# UART_BUS.net
KiCad netlist of a schematic drawn in Altium Designer
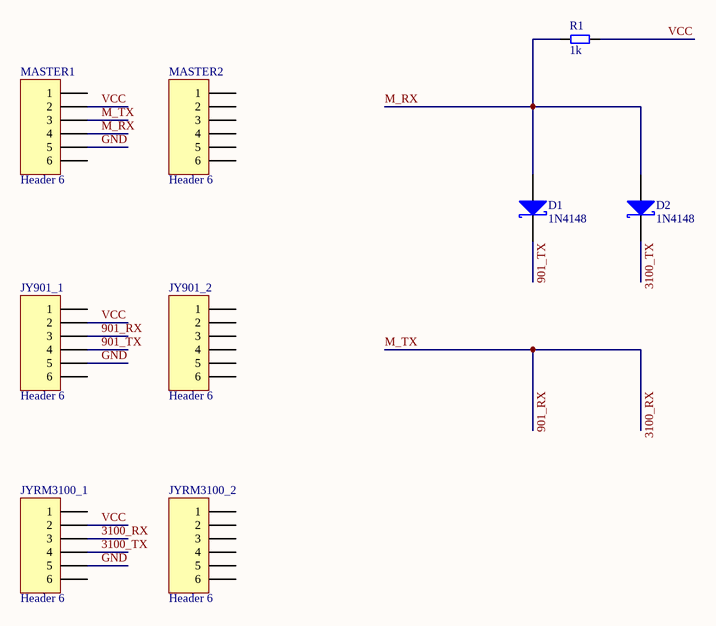
[diagram p0: UART_BUS.SchDoc]

(export (version "E")
  (design (tool "Eeschema 10.0.6"))
  (components
    (comp (ref "D1")
      (value "1N4148")
      (footprint "1N4148_S")
      (description "Schottky Diode")
      (fields (field (name "PUBLISHER") "Altium Limited"))
      (libsource (lib "mosdirver") (part "D Schottky"))
    )
    (comp (ref "D2")
      (value "1N4148")
      (footprint "1N4148_S")
      (description "Schottky Diode")
      (fields (field (name "PUBLISHER") "Altium Limited"))
      (libsource (lib "mosdirver") (part "D Schottky"))
    )
    (comp (ref "JY901_1")
      (value "Device Name")
      (footprint "HDR1X6")
      (description "Header, 6-Pin")
      (fields (field (name "SCH NAME") "Header 6"))
      (libsource (lib "Connector") (part "Header 6"))
    )
    (comp (ref "JY901_2")
      (value "Device Name")
      (footprint "HDR1X6")
      (description "Header, 6-Pin")
      (fields (field (name "SCH NAME") "Header 6"))
      (libsource (lib "Connector") (part "Header 6"))
    )
    (comp (ref "JYRM3100_1")
      (value "Device Name")
      (footprint "HDR1X6")
      (description "Header, 6-Pin")
      (fields (field (name "SCH NAME") "Header 6"))
      (libsource (lib "Connector") (part "Header 6"))
    )
    (comp (ref "JYRM3100_2")
      (value "Device Name")
      (footprint "HDR1X6")
      (description "Header, 6-Pin")
      (fields (field (name "SCH NAME") "Header 6"))
      (libsource (lib "Connector") (part "Header 6"))
    )
    (comp (ref "MASTER1")
      (value "Device Name")
      (footprint "HDR1X6")
      (description "Header, 6-Pin")
      (fields (field (name "SCH NAME") "Header 6"))
      (libsource (lib "Connector") (part "Header 6"))
    )
    (comp (ref "MASTER2")
      (value "Device Name")
      (footprint "HDR1X6")
      (description "Header, 6-Pin")
      (fields (field (name "SCH NAME") "Header 6"))
      (libsource (lib "Connector") (part "Header 6"))
    )
    (comp (ref "R1")
      (value "xxR/Precision/Footprint")
      (footprint "RES 0603")
      (description "Resistor Chip")
      (fields (field (name "SCH NAME") "1k"))
      (libsource (lib "Basal") (part "Resistor Chip"))
    )
  )
  (nets
    (net (code "1") (name "/901_TX") (class "Default")
      (node (ref "D1") (pin "2") (pinfunction "K_2") (pintype "passive"))
      (node (ref "JY901_1") (pin "4") (pinfunction "4_4") (pintype "passive"))
    )
    (net (code "2") (name "/3100_RX") (class "Default")
      (node (ref "JY901_1") (pin "3") (pinfunction "3_3") (pintype "passive"))
      (node (ref "JYRM3100_1") (pin "3") (pinfunction "3_3") (pintype "passive"))
      (node (ref "MASTER1") (pin "3") (pinfunction "3_3") (pintype "passive"))
    )
    (net (code "3") (name "/3100_TX") (class "Default")
      (node (ref "D2") (pin "2") (pinfunction "K_2") (pintype "passive"))
      (node (ref "JYRM3100_1") (pin "4") (pinfunction "4_4") (pintype "passive"))
    )
    (net (code "4") (name "/GND") (class "Default")
      (node (ref "JY901_1") (pin "5") (pinfunction "5_5") (pintype "passive"))
      (node (ref "JYRM3100_1") (pin "5") (pinfunction "5_5") (pintype "passive"))
      (node (ref "MASTER1") (pin "5") (pinfunction "5_5") (pintype "passive"))
    )
    (net (code "5") (name "/M_RX") (class "Default")
      (node (ref "D1") (pin "1") (pinfunction "A_1") (pintype "passive"))
      (node (ref "D2") (pin "1") (pinfunction "A_1") (pintype "passive"))
      (node (ref "MASTER1") (pin "4") (pinfunction "4_4") (pintype "passive"))
      (node (ref "R1") (pin "1") (pintype "passive"))
    )
    (net (code "6") (name "/VCC") (class "Default")
      (node (ref "JY901_1") (pin "2") (pinfunction "2_2") (pintype "passive"))
      (node (ref "JYRM3100_1") (pin "2") (pinfunction "2_2") (pintype "passive"))
      (node (ref "MASTER1") (pin "2") (pinfunction "2_2") (pintype "passive"))
      (node (ref "R1") (pin "2") (pintype "passive"))
    )
    (net (code "7") (name "unconnected-(JY901_1-Pad1)") (class "Default")
      (node (ref "JY901_1") (pin "1") (pinfunction "1_1") (pintype "passive"))
    )
    (net (code "8") (name "unconnected-(JY901_1-Pad6)") (class "Default")
      (node (ref "JY901_1") (pin "6") (pinfunction "6_6") (pintype "passive"))
    )
    (net (code "9") (name "unconnected-(JY901_2-Pad1)") (class "Default")
      (node (ref "JY901_2") (pin "1") (pinfunction "1_1") (pintype "passive"))
    )
    (net (code "10") (name "unconnected-(JY901_2-Pad2)") (class "Default")
      (node (ref "JY901_2") (pin "2") (pinfunction "2_2") (pintype "passive"))
    )
    (net (code "11") (name "unconnected-(JY901_2-Pad3)") (class "Default")
      (node (ref "JY901_2") (pin "3") (pinfunction "3_3") (pintype "passive"))
    )
    (net (code "12") (name "unconnected-(JY901_2-Pad4)") (class "Default")
      (node (ref "JY901_2") (pin "4") (pinfunction "4_4") (pintype "passive"))
    )
    (net (code "13") (name "unconnected-(JY901_2-Pad5)") (class "Default")
      (node (ref "JY901_2") (pin "5") (pinfunction "5_5") (pintype "passive"))
    )
    (net (code "14") (name "unconnected-(JY901_2-Pad6)") (class "Default")
      (node (ref "JY901_2") (pin "6") (pinfunction "6_6") (pintype "passive"))
    )
    (net (code "15") (name "unconnected-(JYRM3100_1-Pad1)") (class "Default")
      (node (ref "JYRM3100_1") (pin "1") (pinfunction "1_1") (pintype "passive"))
    )
    (net (code "16") (name "unconnected-(JYRM3100_1-Pad6)") (class "Default")
      (node (ref "JYRM3100_1") (pin "6") (pinfunction "6_6") (pintype "passive"))
    )
    (net (code "17") (name "unconnected-(JYRM3100_2-Pad1)") (class "Default")
      (node (ref "JYRM3100_2") (pin "1") (pinfunction "1_1") (pintype "passive"))
    )
    (net (code "18") (name "unconnected-(JYRM3100_2-Pad2)") (class "Default")
      (node (ref "JYRM3100_2") (pin "2") (pinfunction "2_2") (pintype "passive"))
    )
    (net (code "19") (name "unconnected-(JYRM3100_2-Pad3)") (class "Default")
      (node (ref "JYRM3100_2") (pin "3") (pinfunction "3_3") (pintype "passive"))
    )
    (net (code "20") (name "unconnected-(JYRM3100_2-Pad4)") (class "Default")
      (node (ref "JYRM3100_2") (pin "4") (pinfunction "4_4") (pintype "passive"))
    )
    (net (code "21") (name "unconnected-(JYRM3100_2-Pad5)") (class "Default")
      (node (ref "JYRM3100_2") (pin "5") (pinfunction "5_5") (pintype "passive"))
    )
    (net (code "22") (name "unconnected-(JYRM3100_2-Pad6)") (class "Default")
      (node (ref "JYRM3100_2") (pin "6") (pinfunction "6_6") (pintype "passive"))
    )
    (net (code "23") (name "unconnected-(MASTER1-Pad1)") (class "Default")
      (node (ref "MASTER1") (pin "1") (pinfunction "1_1") (pintype "passive"))
    )
    (net (code "24") (name "unconnected-(MASTER1-Pad6)") (class "Default")
      (node (ref "MASTER1") (pin "6") (pinfunction "6_6") (pintype "passive"))
    )
    (net (code "25") (name "unconnected-(MASTER2-Pad1)") (class "Default")
      (node (ref "MASTER2") (pin "1") (pinfunction "1_1") (pintype "passive"))
    )
    (net (code "26") (name "unconnected-(MASTER2-Pad2)") (class "Default")
      (node (ref "MASTER2") (pin "2") (pinfunction "2_2") (pintype "passive"))
    )
    (net (code "27") (name "unconnected-(MASTER2-Pad3)") (class "Default")
      (node (ref "MASTER2") (pin "3") (pinfunction "3_3") (pintype "passive"))
    )
    (net (code "28") (name "unconnected-(MASTER2-Pad4)") (class "Default")
      (node (ref "MASTER2") (pin "4") (pinfunction "4_4") (pintype "passive"))
    )
    (net (code "29") (name "unconnected-(MASTER2-Pad5)") (class "Default")
      (node (ref "MASTER2") (pin "5") (pinfunction "5_5") (pintype "passive"))
    )
    (net (code "30") (name "unconnected-(MASTER2-Pad6)") (class "Default")
      (node (ref "MASTER2") (pin "6") (pinfunction "6_6") (pintype "passive"))
    )
  )
)
